# mowgli.net
KiCad netlist of a schematic drawn in EAGLE
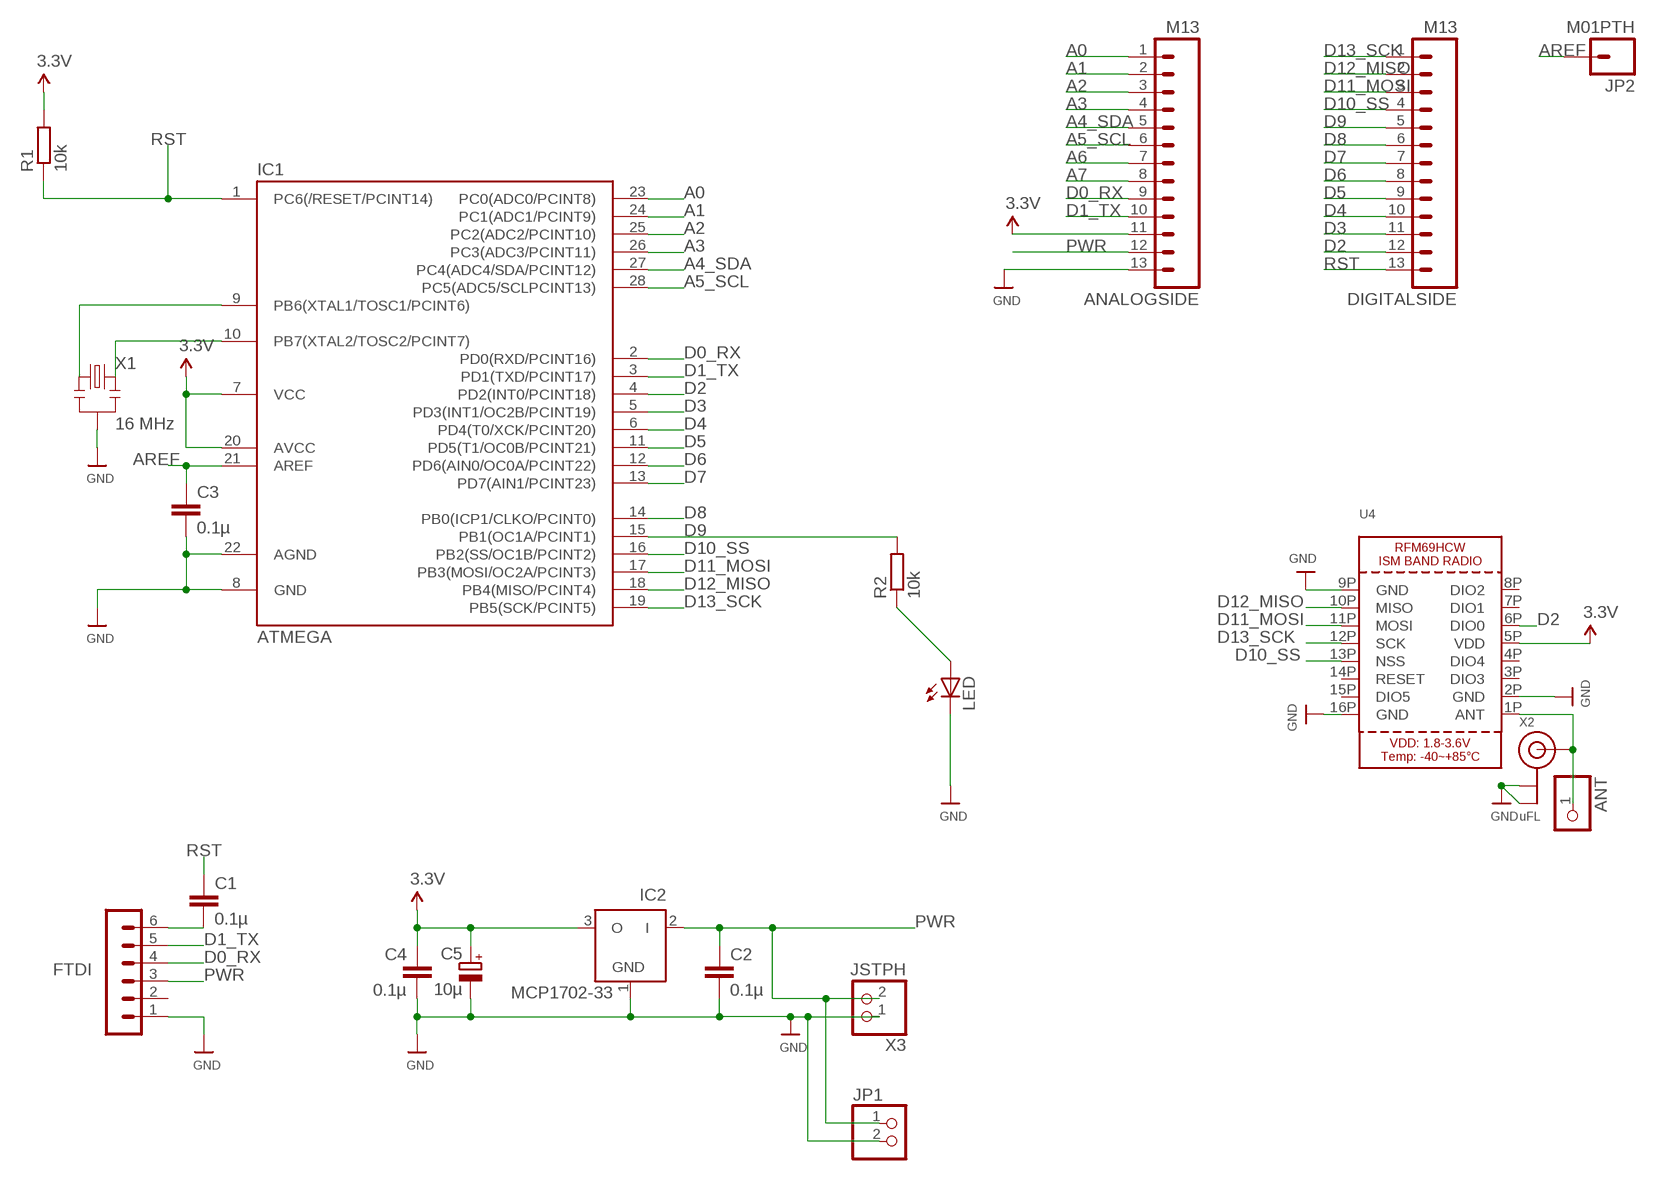
[diagram p0: schematic, sheet 1]

(export (version "E")
  (design (tool "Eeschema 10.0.6"))
  (components
    (comp (ref "ANALOGSIDE")
      (value "M13")
      (footprint "eagle-import:1X13")
      (libsource (lib "eagle-import") (part "M13"))
    )
    (comp (ref "ANT")
      (value "HEADER-1X1ROUND")
      (footprint "eagle-import:1X01_ROUND")
      (libsource (lib "eagle-import") (part "HEADER-1X1ROUND"))
    )
    (comp (ref "C1")
      (value "0.1µ")
      (footprint "eagle-import:C025-024X044")
      (libsource (lib "eagle-import") (part "C-EU025-024X044"))
    )
    (comp (ref "C2")
      (value "0.1µ")
      (footprint "eagle-import:C025-024X044")
      (libsource (lib "eagle-import") (part "C-EU025-024X044"))
    )
    (comp (ref "C3")
      (value "0.1µ")
      (footprint "eagle-import:C025-024X044")
      (libsource (lib "eagle-import") (part "C-EU025-024X044"))
    )
    (comp (ref "C4")
      (value "0.1µ")
      (footprint "eagle-import:C025-024X044")
      (libsource (lib "eagle-import") (part "C-EU025-024X044"))
    )
    (comp (ref "C5")
      (value "10µ")
      (footprint "eagle-import:E1,8-4")
      (libsource (lib "eagle-import") (part "CPOL-EUE1.8-4"))
    )
    (comp (ref "DIGITALSIDE")
      (value "M13")
      (footprint "eagle-import:1X13")
      (libsource (lib "eagle-import") (part "M13"))
    )
    (comp (ref "FTDI")
      (value "FTDI")
      (footprint "eagle-import:MA06-1")
      (libsource (lib "eagle-import") (part "MA06-1"))
    )
    (comp (ref "IC1")
      (value "ATMEGA")
      (footprint "eagle-import:DIL28-3")
      (libsource (lib "eagle-import") (part "ATMEGA48/88/168-PU"))
    )
    (comp (ref "IC2")
      (value "MCP1702-33")
      (footprint "eagle-import:TO92")
      (libsource (lib "eagle-import") (part "MCP1702Z"))
    )
    (comp (ref "JP1")
      (value "PINHD-1X2")
      (footprint "eagle-import:1X02")
      (libsource (lib "eagle-import") (part "PINHD-1X2"))
    )
    (comp (ref "JP2")
      (value "M01PTH")
      (footprint "eagle-import:1X01")
      (libsource (lib "eagle-import") (part "M01PTH"))
    )
    (comp (ref "LED")
      (value "LED3MM")
      (footprint "eagle-import:LED3MM")
      (libsource (lib "eagle-import") (part "LED3MM"))
    )
    (comp (ref "R1")
      (value "10k")
      (footprint "eagle-import:0204_7")
      (libsource (lib "eagle-import") (part "R-EU_0204/7"))
    )
    (comp (ref "R2")
      (value "10k")
      (footprint "eagle-import:0204_7")
      (libsource (lib "eagle-import") (part "R-EU_0204/7"))
    )
    (comp (ref "U4")
      (value "RFM69HCW_SMT")
      (footprint "eagle-import:RFMHCW_SMT")
      (libsource (lib "eagle-import") (part "RFM69HCW_SMT"))
    )
    (comp (ref "X1")
      (value "16 MHz")
      (footprint "eagle-import:RESONATOR-PTH")
      (libsource (lib "eagle-import") (part "RESONATORPTH"))
    )
    (comp (ref "X2")
      (value "uFL")
      (footprint "eagle-import:U.FL")
      (libsource (lib "eagle-import") (part "ANTENNA_U.FL"))
    )
    (comp (ref "X3")
      (value "JSTPH")
      (footprint "eagle-import:JSTPH2")
      (libsource (lib "eagle-import") (part "CON_JST_PH_2PIN"))
    )
  )
  (nets
    (net (code "1") (name "/A0") (class "Default")
      (node (ref "ANALOGSIDE") (pin "1") (pinfunction "1_1") (pintype "passive"))
      (node (ref "IC1") (pin "23") (pinfunction "PC0(ADC0/PCINT8)_23") (pintype "bidirectional"))
    )
    (net (code "2") (name "/A1") (class "Default")
      (node (ref "ANALOGSIDE") (pin "2") (pinfunction "2_2") (pintype "passive"))
      (node (ref "IC1") (pin "24") (pinfunction "PC1(ADC1/PCINT9)_24") (pintype "bidirectional"))
    )
    (net (code "3") (name "/A2") (class "Default")
      (node (ref "ANALOGSIDE") (pin "3") (pinfunction "3_3") (pintype "passive"))
      (node (ref "IC1") (pin "25") (pinfunction "PC2(ADC2/PCINT10)_25") (pintype "bidirectional"))
    )
    (net (code "4") (name "/A3") (class "Default")
      (node (ref "ANALOGSIDE") (pin "4") (pinfunction "4_4") (pintype "passive"))
      (node (ref "IC1") (pin "26") (pinfunction "PC3(ADC3/PCINT11)_26") (pintype "bidirectional"))
    )
    (net (code "5") (name "/A4_SDA") (class "Default")
      (node (ref "ANALOGSIDE") (pin "5") (pinfunction "5_5") (pintype "passive"))
      (node (ref "IC1") (pin "27") (pinfunction "PC4(ADC4/SDA/PCINT12)_27") (pintype "bidirectional"))
    )
    (net (code "6") (name "/A5_SCL") (class "Default")
      (node (ref "ANALOGSIDE") (pin "6") (pinfunction "6_6") (pintype "passive"))
      (node (ref "IC1") (pin "28") (pinfunction "PC5(ADC5/SCLPCINT13)_28") (pintype "bidirectional"))
    )
    (net (code "7") (name "/A6") (class "Default")
      (node (ref "ANALOGSIDE") (pin "7") (pinfunction "7_7") (pintype "passive"))
    )
    (net (code "8") (name "/A7") (class "Default")
      (node (ref "ANALOGSIDE") (pin "8") (pinfunction "8_8") (pintype "passive"))
    )
    (net (code "9") (name "/AREF") (class "Default")
      (node (ref "C3") (pin "1") (pinfunction "1_1") (pintype "passive"))
      (node (ref "IC1") (pin "21") (pinfunction "AREF_21") (pintype "passive"))
      (node (ref "JP2") (pin "1") (pinfunction "1_1") (pintype "passive"))
    )
    (net (code "10") (name "/D0_RX") (class "Default")
      (node (ref "ANALOGSIDE") (pin "9") (pinfunction "9_9") (pintype "passive"))
      (node (ref "FTDI") (pin "4") (pinfunction "4_4") (pintype "passive"))
      (node (ref "IC1") (pin "2") (pinfunction "PD0(RXD/PCINT16)_2") (pintype "bidirectional"))
    )
    (net (code "11") (name "/D1_TX") (class "Default")
      (node (ref "ANALOGSIDE") (pin "10") (pinfunction "10_10") (pintype "passive"))
      (node (ref "FTDI") (pin "5") (pinfunction "5_5") (pintype "passive"))
      (node (ref "IC1") (pin "3") (pinfunction "PD1(TXD/PCINT17)_3") (pintype "bidirectional"))
    )
    (net (code "12") (name "/D2") (class "Default")
      (node (ref "DIGITALSIDE") (pin "12") (pinfunction "12_12") (pintype "passive"))
      (node (ref "IC1") (pin "4") (pinfunction "PD2(INT0/PCINT18)_4") (pintype "bidirectional"))
      (node (ref "U4") (pin "6P") (pinfunction "DIO0_6P") (pintype "bidirectional"))
    )
    (net (code "13") (name "/D3") (class "Default")
      (node (ref "DIGITALSIDE") (pin "11") (pinfunction "11_11") (pintype "passive"))
      (node (ref "IC1") (pin "5") (pinfunction "PD3(INT1/OC2B/PCINT19)_5") (pintype "bidirectional"))
    )
    (net (code "14") (name "/D4") (class "Default")
      (node (ref "DIGITALSIDE") (pin "10") (pinfunction "10_10") (pintype "passive"))
      (node (ref "IC1") (pin "6") (pinfunction "PD4(T0/XCK/PCINT20)_6") (pintype "bidirectional"))
    )
    (net (code "15") (name "/D5") (class "Default")
      (node (ref "DIGITALSIDE") (pin "9") (pinfunction "9_9") (pintype "passive"))
      (node (ref "IC1") (pin "11") (pinfunction "PD5(T1/OC0B/PCINT21)_11") (pintype "bidirectional"))
    )
    (net (code "16") (name "/D6") (class "Default")
      (node (ref "DIGITALSIDE") (pin "8") (pinfunction "8_8") (pintype "passive"))
      (node (ref "IC1") (pin "12") (pinfunction "PD6(AIN0/OC0A/PCINT22)_12") (pintype "bidirectional"))
    )
    (net (code "17") (name "/D7") (class "Default")
      (node (ref "DIGITALSIDE") (pin "7") (pinfunction "7_7") (pintype "passive"))
      (node (ref "IC1") (pin "13") (pinfunction "PD7(AIN1/PCINT23)_13") (pintype "bidirectional"))
    )
    (net (code "18") (name "/D8") (class "Default")
      (node (ref "DIGITALSIDE") (pin "6") (pinfunction "6_6") (pintype "passive"))
      (node (ref "IC1") (pin "14") (pinfunction "PB0(ICP1/CLKO/PCINT0)_14") (pintype "bidirectional"))
    )
    (net (code "19") (name "/D9") (class "Default")
      (node (ref "DIGITALSIDE") (pin "5") (pinfunction "5_5") (pintype "passive"))
      (node (ref "IC1") (pin "15") (pinfunction "PB1(OC1A/PCINT1)_15") (pintype "bidirectional"))
      (node (ref "R2") (pin "2") (pinfunction "2_2") (pintype "passive"))
    )
    (net (code "20") (name "/D10_SS") (class "Default")
      (node (ref "DIGITALSIDE") (pin "4") (pinfunction "4_4") (pintype "passive"))
      (node (ref "IC1") (pin "16") (pinfunction "PB2(SS/OC1B/PCINT2)_16") (pintype "bidirectional"))
      (node (ref "U4") (pin "13P") (pinfunction "NSS_13P") (pintype "input"))
    )
    (net (code "21") (name "/D11_MOSI") (class "Default")
      (node (ref "DIGITALSIDE") (pin "3") (pinfunction "3_3") (pintype "passive"))
      (node (ref "IC1") (pin "17") (pinfunction "PB3(MOSI/OC2A/PCINT3)_17") (pintype "bidirectional"))
      (node (ref "U4") (pin "11P") (pinfunction "MOSI_11P") (pintype "input"))
    )
    (net (code "22") (name "/D12_MISO") (class "Default")
      (node (ref "DIGITALSIDE") (pin "2") (pinfunction "2_2") (pintype "passive"))
      (node (ref "IC1") (pin "18") (pinfunction "PB4(MISO/PCINT4)_18") (pintype "bidirectional"))
      (node (ref "U4") (pin "10P") (pinfunction "MISO_10P") (pintype "output"))
    )
    (net (code "23") (name "/D13_SCK") (class "Default")
      (node (ref "DIGITALSIDE") (pin "1") (pinfunction "1_1") (pintype "passive"))
      (node (ref "IC1") (pin "19") (pinfunction "PB5(SCK/PCINT5)_19") (pintype "bidirectional"))
      (node (ref "U4") (pin "12P") (pinfunction "SCK_12P") (pintype "input"))
    )
    (net (code "24") (name "/PWR") (class "Default")
      (node (ref "ANALOGSIDE") (pin "12") (pinfunction "12_12") (pintype "passive"))
      (node (ref "C2") (pin "1") (pinfunction "1_1") (pintype "passive"))
      (node (ref "FTDI") (pin "3") (pinfunction "3_3") (pintype "passive"))
      (node (ref "IC2") (pin "2") (pinfunction "I_2") (pintype "input"))
      (node (ref "JP1") (pin "1") (pinfunction "1_1") (pintype "passive"))
      (node (ref "X3") (pin "2") (pinfunction "2_2") (pintype "passive"))
    )
    (net (code "25") (name "/RST") (class "Default")
      (node (ref "C1") (pin "1") (pinfunction "1_1") (pintype "passive"))
      (node (ref "DIGITALSIDE") (pin "13") (pinfunction "13_13") (pintype "passive"))
      (node (ref "IC1") (pin "1") (pinfunction "PC6(/RESET/PCINT14)_1") (pintype "bidirectional"))
      (node (ref "R1") (pin "1") (pinfunction "1_1") (pintype "passive"))
    )
    (net (code "26") (name "3.3V") (class "Default")
      (node (ref "ANALOGSIDE") (pin "11") (pinfunction "11_11") (pintype "passive"))
      (node (ref "C4") (pin "1") (pinfunction "1_1") (pintype "passive"))
      (node (ref "C5") (pin "+") (pinfunction "+_+") (pintype "passive"))
      (node (ref "IC1") (pin "20") (pinfunction "AVCC_20") (pintype "passive"))
      (node (ref "IC1") (pin "7") (pinfunction "VCC_7") (pintype "power_in"))
      (node (ref "IC2") (pin "3") (pinfunction "O_3") (pintype "input"))
      (node (ref "R1") (pin "2") (pinfunction "2_2") (pintype "passive"))
      (node (ref "U4") (pin "5P") (pinfunction "VDD_5P") (pintype "power_in"))
    )
    (net (code "27") (name "GND") (class "Default")
      (node (ref "ANALOGSIDE") (pin "13") (pinfunction "13_13") (pintype "passive"))
      (node (ref "C2") (pin "2") (pinfunction "2_2") (pintype "passive"))
      (node (ref "C3") (pin "2") (pinfunction "2_2") (pintype "passive"))
      (node (ref "C4") (pin "2") (pinfunction "2_2") (pintype "passive"))
      (node (ref "C5") (pin "-") (pinfunction "-_-") (pintype "passive"))
      (node (ref "FTDI") (pin "1") (pinfunction "1_1") (pintype "passive"))
      (node (ref "IC1") (pin "22") (pinfunction "AGND_22") (pintype "power_in"))
      (node (ref "IC1") (pin "8") (pinfunction "GND_8") (pintype "power_in"))
      (node (ref "IC2") (pin "1") (pinfunction "GND_1") (pintype "power_in"))
      (node (ref "JP1") (pin "2") (pinfunction "2_2") (pintype "passive"))
      (node (ref "LED") (pin "K") (pinfunction "C_K") (pintype "passive"))
      (node (ref "U4") (pin "16P") (pinfunction "GND_16P") (pintype "power_in"))
      (node (ref "U4") (pin "2P") (pinfunction "GND_2P") (pintype "power_in"))
      (node (ref "U4") (pin "9P") (pinfunction "GND_9P") (pintype "power_in"))
      (node (ref "X1") (pin "2") (pinfunction "2_2") (pintype "passive"))
      (node (ref "X2") (pin "1") (pinfunction "GND_1") (pintype "passive"))
      (node (ref "X2") (pin "2") (pinfunction "GND_2") (pintype "passive"))
      (node (ref "X3") (pin "1") (pinfunction "1_1") (pintype "passive"))
    )
    (net (code "28") (name "Net-(C1-Pad2)") (class "Default")
      (node (ref "C1") (pin "2") (pinfunction "2_2") (pintype "passive"))
      (node (ref "FTDI") (pin "6") (pinfunction "6_6") (pintype "passive"))
    )
    (net (code "29") (name "Net-(IC1-PB6(XTAL1{slash}TOSC1{slash}PCINT6))") (class "Default")
      (node (ref "IC1") (pin "9") (pinfunction "PB6(XTAL1/TOSC1/PCINT6)_9") (pintype "bidirectional"))
      (node (ref "X1") (pin "1") (pinfunction "1_1") (pintype "passive"))
    )
    (net (code "30") (name "Net-(IC1-PB7(XTAL2{slash}TOSC2{slash}PCINT7))") (class "Default")
      (node (ref "IC1") (pin "10") (pinfunction "PB7(XTAL2/TOSC2/PCINT7)_10") (pintype "bidirectional"))
      (node (ref "X1") (pin "3") (pinfunction "3_3") (pintype "passive"))
    )
    (net (code "31") (name "Net-(LED-PadA)") (class "Default")
      (node (ref "LED") (pin "A") (pinfunction "A_A") (pintype "passive"))
      (node (ref "R2") (pin "1") (pinfunction "1_1") (pintype "passive"))
    )
    (net (code "32") (name "Net-(U4-ANT)") (class "Default")
      (node (ref "ANT") (pin "1") (pinfunction "1_1") (pintype "passive"))
      (node (ref "U4") (pin "1P") (pinfunction "ANT_1P") (pintype "bidirectional"))
      (node (ref "X2") (pin "3") (pinfunction "SIGNAL_3") (pintype "passive"))
    )
    (net (code "33") (name "unconnected-(FTDI-Pad2)") (class "Default")
      (node (ref "FTDI") (pin "2") (pinfunction "2_2") (pintype "passive"))
    )
    (net (code "34") (name "unconnected-(U4-DIO1-Pad7P)") (class "Default")
      (node (ref "U4") (pin "7P") (pinfunction "DIO1_7P") (pintype "bidirectional"))
    )
    (net (code "35") (name "unconnected-(U4-DIO2-Pad8P)") (class "Default")
      (node (ref "U4") (pin "8P") (pinfunction "DIO2_8P") (pintype "bidirectional"))
    )
    (net (code "36") (name "unconnected-(U4-DIO3-Pad3P)") (class "Default")
      (node (ref "U4") (pin "3P") (pinfunction "DIO3_3P") (pintype "bidirectional"))
    )
    (net (code "37") (name "unconnected-(U4-DIO4-Pad4P)") (class "Default")
      (node (ref "U4") (pin "4P") (pinfunction "DIO4_4P") (pintype "bidirectional"))
    )
    (net (code "38") (name "unconnected-(U4-DIO5-Pad15P)") (class "Default")
      (node (ref "U4") (pin "15P") (pinfunction "DIO5_15P") (pintype "bidirectional"))
    )
    (net (code "39") (name "unconnected-(U4-RESET-Pad14P)") (class "Default")
      (node (ref "U4") (pin "14P") (pinfunction "RESET_14P") (pintype "input"))
    )
  )
)
